# USBASP.net
KiCad netlist of a schematic drawn in EAGLE
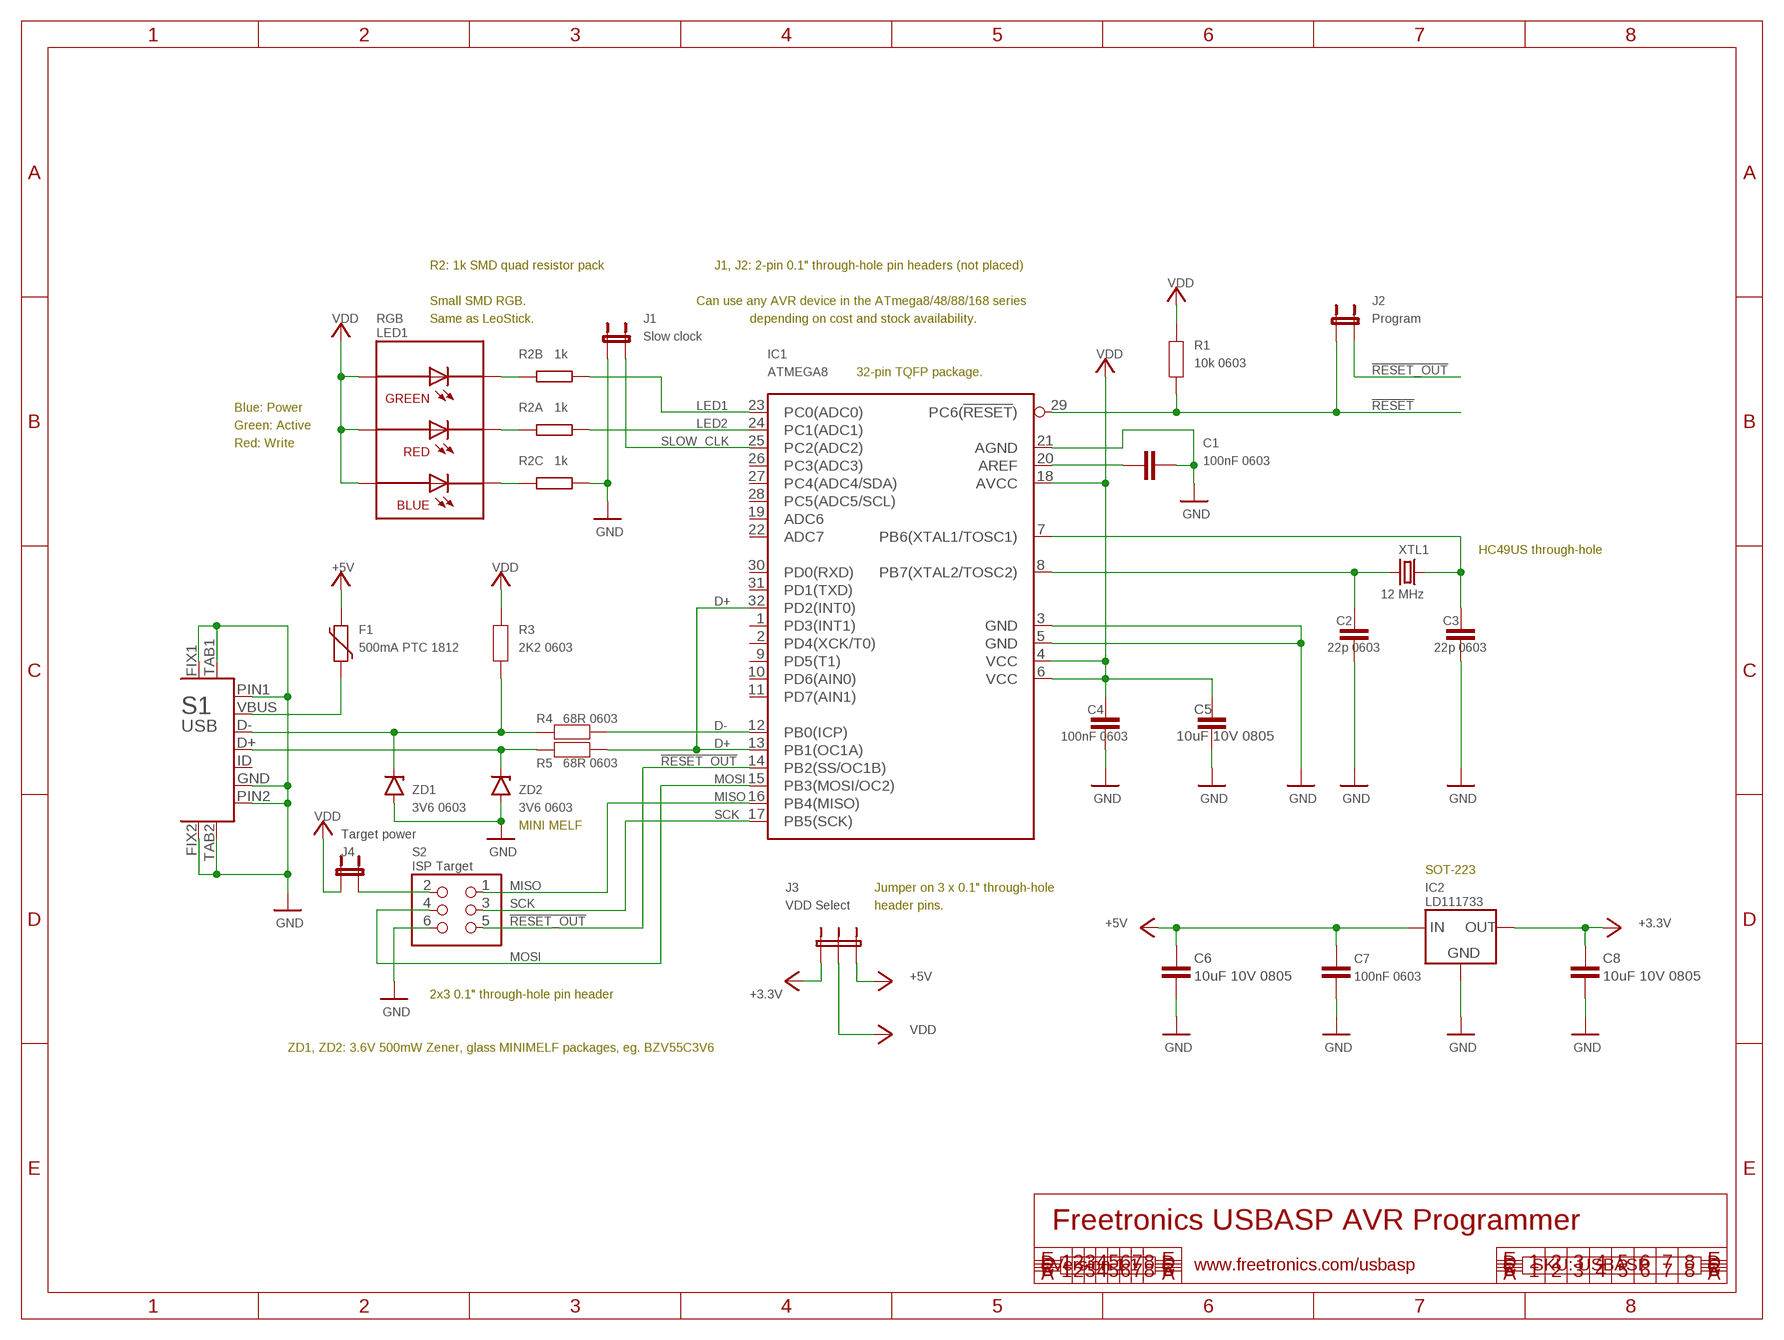
[diagram p0: schematic, sheet 1]

(export (version "E")
  (design (tool "Eeschema 10.0.6"))
  (components
    (comp (ref "C1")
      (value "100nF 0603")
      (footprint "eagle-import:0603")
      (libsource (lib "eagle-import") (part "CAP0603"))
    )
    (comp (ref "C2")
      (value "22p 0603")
      (footprint "eagle-import:0603")
      (libsource (lib "eagle-import") (part "CAP0603"))
    )
    (comp (ref "C3")
      (value "22p 0603")
      (footprint "eagle-import:0603")
      (libsource (lib "eagle-import") (part "CAP0603"))
    )
    (comp (ref "C4")
      (value "100nF 0603")
      (footprint "eagle-import:0603")
      (libsource (lib "eagle-import") (part "CAP0603"))
    )
    (comp (ref "C5")
      (value "10uF 10V 0805")
      (footprint "eagle-import:C0805")
      (libsource (lib "eagle-import") (part "C-EUC0805"))
    )
    (comp (ref "C6")
      (value "10uF 10V 0805")
      (footprint "eagle-import:C0805")
      (libsource (lib "eagle-import") (part "C-EUC0805"))
    )
    (comp (ref "C7")
      (value "100nF 0603")
      (footprint "eagle-import:0603")
      (libsource (lib "eagle-import") (part "CAP0603"))
    )
    (comp (ref "C8")
      (value "10uF 10V 0805")
      (footprint "eagle-import:C0805")
      (libsource (lib "eagle-import") (part "C-EUC0805"))
    )
    (comp (ref "F1")
      (value "500mA PTC 1812")
      (footprint "eagle-import:1812")
      (libsource (lib "eagle-import") (part "PTC"))
    )
    (comp (ref "IC1")
      (value "ATMEGA8")
      (footprint "eagle-import:TQFP32-08")
      (libsource (lib "eagle-import") (part "ATMEGA168"))
    )
    (comp (ref "IC2")
      (value "LD111733")
      (footprint "eagle-import:SOT-223")
      (libsource (lib "eagle-import") (part "LD1117-FIXED"))
    )
    (comp (ref "J1")
      (value "Slow clock")
      (footprint "eagle-import:HEADER_1X02")
      (libsource (lib "eagle-import") (part "JUMPER_PTH"))
    )
    (comp (ref "J2")
      (value "Program")
      (footprint "eagle-import:HEADER_1X02")
      (libsource (lib "eagle-import") (part "JUMPER_PTH"))
    )
    (comp (ref "J3")
      (value "VDD Select")
      (footprint "eagle-import:JUMPER_SPDT")
      (libsource (lib "eagle-import") (part "JUMPER_SPDT"))
    )
    (comp (ref "J4")
      (value "Target power")
      (footprint "eagle-import:HEADER_1X02")
      (libsource (lib "eagle-import") (part "JUMPER_PTH"))
    )
    (comp (ref "LED1")
      (value "RGB")
      (footprint "eagle-import:19-337")
      (libsource (lib "eagle-import") (part "RGBLEDSMT"))
    )
    (comp (ref "R1")
      (value "10k 0603")
      (footprint "eagle-import:0603")
      (libsource (lib "eagle-import") (part "RESISTOR0603"))
    )
    (comp (ref "R2")
      (value "1k")
      (footprint "eagle-import:CAY16")
      (libsource (lib "eagle-import") (part "CAY16"))
    )
    (comp (ref "R3")
      (value "2K2 0603")
      (footprint "eagle-import:0603")
      (libsource (lib "eagle-import") (part "RESISTOR0603"))
    )
    (comp (ref "R4")
      (value "68R 0603")
      (footprint "eagle-import:0603")
      (libsource (lib "eagle-import") (part "RESISTOR0603"))
    )
    (comp (ref "R5")
      (value "68R 0603")
      (footprint "eagle-import:0603")
      (libsource (lib "eagle-import") (part "RESISTOR0603"))
    )
    (comp (ref "S1")
      (value "USB")
      (footprint "eagle-import:USB-MICROB-MB05PMXX")
      (libsource (lib "eagle-import") (part "USB-6PSMT"))
    )
    (comp (ref "S2")
      (value "ISP Target")
      (footprint "eagle-import:HEADER_2X3")
      (libsource (lib "eagle-import") (part "HEADER_2X3"))
    )
    (comp (ref "XTL1")
      (value "12 MHz")
      (footprint "eagle-import:HC49US")
      (libsource (lib "eagle-import") (part "CRYSTALHC49US"))
    )
    (comp (ref "ZD1")
      (value "3V6 0603")
      (footprint "eagle-import:MINIMELF")
      (libsource (lib "eagle-import") (part "ZENERMINIMELF"))
    )
    (comp (ref "ZD2")
      (value "3V6 0603")
      (footprint "eagle-import:MINIMELF")
      (libsource (lib "eagle-import") (part "ZENERMINIMELF"))
    )
  )
  (nets
    (net (code "1") (name "+3.3V") (class "Default")
      (node (ref "C8") (pin "1") (pinfunction "1_1") (pintype "passive"))
      (node (ref "IC2") (pin "2") (pinfunction "OUT_2") (pintype "power_in"))
      (node (ref "IC2") (pin "4") (pinfunction "OUT_4") (pintype "power_in"))
      (node (ref "J3") (pin "1") (pinfunction "1_1") (pintype "passive"))
    )
    (net (code "2") (name "+5V") (class "Default")
      (node (ref "C6") (pin "1") (pinfunction "1_1") (pintype "passive"))
      (node (ref "C7") (pin "1") (pinfunction "1_1") (pintype "passive"))
      (node (ref "F1") (pin "2") (pinfunction "P$2_2") (pintype "bidirectional"))
      (node (ref "IC2") (pin "3") (pinfunction "IN_3") (pintype "input"))
      (node (ref "J3") (pin "3") (pinfunction "3_3") (pintype "passive"))
    )
    (net (code "3") (name "/D+") (class "Default")
      (node (ref "IC1") (pin "13") (pinfunction "PB1(OC1A)_13") (pintype "bidirectional"))
      (node (ref "IC1") (pin "32") (pinfunction "PD2(INT0)_32") (pintype "bidirectional"))
      (node (ref "R5") (pin "1") (pinfunction "1_1") (pintype "passive"))
    )
    (net (code "4") (name "/D-") (class "Default")
      (node (ref "IC1") (pin "12") (pinfunction "PB0(ICP)_12") (pintype "bidirectional"))
      (node (ref "R4") (pin "1") (pinfunction "1_1") (pintype "passive"))
    )
    (net (code "5") (name "/LED1") (class "Default")
      (node (ref "IC1") (pin "23") (pinfunction "PC0(ADC0)_23") (pintype "bidirectional"))
      (node (ref "R2") (pin "2") (pinfunction "1_2") (pintype "passive"))
    )
    (net (code "6") (name "/LED2") (class "Default")
      (node (ref "IC1") (pin "24") (pinfunction "PC1(ADC1)_24") (pintype "bidirectional"))
      (node (ref "R2") (pin "1") (pinfunction "1_1") (pintype "passive"))
    )
    (net (code "7") (name "/MISO") (class "Default")
      (node (ref "IC1") (pin "16") (pinfunction "PB4(MISO)_16") (pintype "bidirectional"))
      (node (ref "S2") (pin "1") (pinfunction "1_1") (pintype "passive"))
    )
    (net (code "8") (name "/MOSI") (class "Default")
      (node (ref "IC1") (pin "15") (pinfunction "PB3(MOSI/OC2)_15") (pintype "bidirectional"))
      (node (ref "S2") (pin "4") (pinfunction "4_4") (pintype "passive"))
    )
    (net (code "9") (name "/SCK") (class "Default")
      (node (ref "IC1") (pin "17") (pinfunction "PB5(SCK)_17") (pintype "bidirectional"))
      (node (ref "S2") (pin "3") (pinfunction "3_3") (pintype "passive"))
    )
    (net (code "10") (name "/SLOW_CLK") (class "Default")
      (node (ref "IC1") (pin "25") (pinfunction "PC2(ADC2)_25") (pintype "bidirectional"))
      (node (ref "J1") (pin "2") (pinfunction "2_2") (pintype "passive"))
    )
    (net (code "11") (name "/~{RESET_OUT}") (class "Default")
      (node (ref "IC1") (pin "14") (pinfunction "PB2(SS/OC1B)_14") (pintype "bidirectional"))
      (node (ref "J2") (pin "2") (pinfunction "2_2") (pintype "passive"))
      (node (ref "S2") (pin "5") (pinfunction "5_5") (pintype "passive"))
    )
    (net (code "12") (name "/~{RESET}") (class "Default")
      (node (ref "IC1") (pin "29") (pinfunction "PC6(~{RESET})_29") (pintype "bidirectional"))
      (node (ref "J2") (pin "1") (pinfunction "1_1") (pintype "passive"))
      (node (ref "R1") (pin "1") (pinfunction "1_1") (pintype "passive"))
    )
    (net (code "13") (name "GND") (class "Default")
      (node (ref "C1") (pin "2") (pinfunction "2_2") (pintype "passive"))
      (node (ref "C2") (pin "1") (pinfunction "1_1") (pintype "passive"))
      (node (ref "C3") (pin "1") (pinfunction "1_1") (pintype "passive"))
      (node (ref "C4") (pin "2") (pinfunction "2_2") (pintype "passive"))
      (node (ref "C5") (pin "2") (pinfunction "2_2") (pintype "passive"))
      (node (ref "C6") (pin "2") (pinfunction "2_2") (pintype "passive"))
      (node (ref "C7") (pin "2") (pinfunction "2_2") (pintype "passive"))
      (node (ref "C8") (pin "2") (pinfunction "2_2") (pintype "passive"))
      (node (ref "IC1") (pin "21") (pinfunction "AGND_21") (pintype "bidirectional"))
      (node (ref "IC1") (pin "3") (pinfunction "GND_3") (pintype "bidirectional"))
      (node (ref "IC1") (pin "5") (pinfunction "GND_5") (pintype "bidirectional"))
      (node (ref "IC2") (pin "1") (pinfunction "GND_1") (pintype "input"))
      (node (ref "J1") (pin "1") (pinfunction "1_1") (pintype "passive"))
      (node (ref "R2") (pin "3") (pinfunction "1_3") (pintype "passive"))
      (node (ref "S1") (pin "FIX1") (pinfunction "FIX1_FIX1") (pintype "bidirectional"))
      (node (ref "S1") (pin "FIX2") (pinfunction "FIX2_FIX2") (pintype "bidirectional"))
      (node (ref "S1") (pin "GND") (pinfunction "GND_GND") (pintype "bidirectional"))
      (node (ref "S1") (pin "PIN1") (pinfunction "PIN1_PIN1") (pintype "bidirectional"))
      (node (ref "S1") (pin "PIN2") (pinfunction "PIN2_PIN2") (pintype "bidirectional"))
      (node (ref "S1") (pin "TAB1") (pinfunction "TAB1_TAB1") (pintype "bidirectional"))
      (node (ref "S1") (pin "TAB2") (pinfunction "TAB2_TAB2") (pintype "bidirectional"))
      (node (ref "S2") (pin "6") (pinfunction "6_6") (pintype "passive"))
      (node (ref "ZD1") (pin "A") (pinfunction "A_A") (pintype "passive"))
      (node (ref "ZD2") (pin "A") (pinfunction "A_A") (pintype "passive"))
    )
    (net (code "14") (name "Net-(F1-P$1)") (class "Default")
      (node (ref "F1") (pin "1") (pinfunction "P$1_1") (pintype "bidirectional"))
      (node (ref "S1") (pin "VBUS") (pinfunction "VBUS_VBUS") (pintype "bidirectional"))
    )
    (net (code "15") (name "Net-(IC1-AREF)") (class "Default")
      (node (ref "C1") (pin "1") (pinfunction "1_1") (pintype "passive"))
      (node (ref "IC1") (pin "20") (pinfunction "AREF_20") (pintype "bidirectional"))
    )
    (net (code "16") (name "Net-(IC1-PB6(XTAL1{slash}TOSC1))") (class "Default")
      (node (ref "C3") (pin "2") (pinfunction "2_2") (pintype "passive"))
      (node (ref "IC1") (pin "7") (pinfunction "PB6(XTAL1/TOSC1)_7") (pintype "bidirectional"))
      (node (ref "XTL1") (pin "2") (pinfunction "2_2") (pintype "passive"))
    )
    (net (code "17") (name "Net-(IC1-PB7(XTAL2{slash}TOSC2))") (class "Default")
      (node (ref "C2") (pin "2") (pinfunction "2_2") (pintype "passive"))
      (node (ref "IC1") (pin "8") (pinfunction "PB7(XTAL2/TOSC2)_8") (pintype "bidirectional"))
      (node (ref "XTL1") (pin "1") (pinfunction "1_1") (pintype "passive"))
    )
    (net (code "18") (name "Net-(J4-Pad2)") (class "Default")
      (node (ref "J4") (pin "2") (pinfunction "2_2") (pintype "passive"))
      (node (ref "S2") (pin "2") (pinfunction "2_2") (pintype "passive"))
    )
    (net (code "19") (name "Net-(LED1-C-B)") (class "Default")
      (node (ref "LED1") (pin "1") (pinfunction "C-B_1") (pintype "passive"))
      (node (ref "R2") (pin "6") (pinfunction "2_6") (pintype "passive"))
    )
    (net (code "20") (name "Net-(LED1-C-G)") (class "Default")
      (node (ref "LED1") (pin "3") (pinfunction "C-G_3") (pintype "passive"))
      (node (ref "R2") (pin "7") (pinfunction "2_7") (pintype "passive"))
    )
    (net (code "21") (name "Net-(LED1-C-R)") (class "Default")
      (node (ref "LED1") (pin "2") (pinfunction "C-R_2") (pintype "passive"))
      (node (ref "R2") (pin "8") (pinfunction "2_8") (pintype "passive"))
    )
    (net (code "22") (name "Net-(R3-Pad1)") (class "Default")
      (node (ref "R3") (pin "1") (pinfunction "1_1") (pintype "passive"))
      (node (ref "R4") (pin "2") (pinfunction "2_2") (pintype "passive"))
      (node (ref "S1") (pin "D-") (pinfunction "D-_D-") (pintype "bidirectional"))
      (node (ref "ZD1") (pin "K") (pinfunction "K_K") (pintype "passive"))
    )
    (net (code "23") (name "Net-(R5-Pad2)") (class "Default")
      (node (ref "R5") (pin "2") (pinfunction "2_2") (pintype "passive"))
      (node (ref "S1") (pin "D+") (pinfunction "D+_D+") (pintype "bidirectional"))
      (node (ref "ZD2") (pin "K") (pinfunction "K_K") (pintype "passive"))
    )
    (net (code "24") (name "VDD") (class "Default")
      (node (ref "C4") (pin "1") (pinfunction "1_1") (pintype "passive"))
      (node (ref "C5") (pin "1") (pinfunction "1_1") (pintype "passive"))
      (node (ref "IC1") (pin "18") (pinfunction "AVCC_18") (pintype "bidirectional"))
      (node (ref "IC1") (pin "4") (pinfunction "VCC_4") (pintype "bidirectional"))
      (node (ref "IC1") (pin "6") (pinfunction "VCC_6") (pintype "bidirectional"))
      (node (ref "J3") (pin "2") (pinfunction "2_2") (pintype "passive"))
      (node (ref "J4") (pin "1") (pinfunction "1_1") (pintype "passive"))
      (node (ref "LED1") (pin "4") (pinfunction "A-B_4") (pintype "passive"))
      (node (ref "LED1") (pin "5") (pinfunction "A-R_5") (pintype "passive"))
      (node (ref "LED1") (pin "6") (pinfunction "A-G_6") (pintype "passive"))
      (node (ref "R1") (pin "2") (pinfunction "2_2") (pintype "passive"))
      (node (ref "R3") (pin "2") (pinfunction "2_2") (pintype "passive"))
    )
    (net (code "25") (name "unconnected-(IC1-ADC6-Pad19)") (class "Default")
      (node (ref "IC1") (pin "19") (pinfunction "ADC6_19") (pintype "bidirectional"))
    )
    (net (code "26") (name "unconnected-(IC1-ADC7-Pad22)") (class "Default")
      (node (ref "IC1") (pin "22") (pinfunction "ADC7_22") (pintype "bidirectional"))
    )
    (net (code "27") (name "unconnected-(IC1-PC3(ADC3)-Pad26)") (class "Default")
      (node (ref "IC1") (pin "26") (pinfunction "PC3(ADC3)_26") (pintype "bidirectional"))
    )
    (net (code "28") (name "unconnected-(IC1-PC4(ADC4{slash}SDA)-Pad27)") (class "Default")
      (node (ref "IC1") (pin "27") (pinfunction "PC4(ADC4/SDA)_27") (pintype "bidirectional"))
    )
    (net (code "29") (name "unconnected-(IC1-PC5(ADC5{slash}SCL)-Pad28)") (class "Default")
      (node (ref "IC1") (pin "28") (pinfunction "PC5(ADC5/SCL)_28") (pintype "bidirectional"))
    )
    (net (code "30") (name "unconnected-(IC1-PD0(RXD)-Pad30)") (class "Default")
      (node (ref "IC1") (pin "30") (pinfunction "PD0(RXD)_30") (pintype "bidirectional"))
    )
    (net (code "31") (name "unconnected-(IC1-PD1(TXD)-Pad31)") (class "Default")
      (node (ref "IC1") (pin "31") (pinfunction "PD1(TXD)_31") (pintype "bidirectional"))
    )
    (net (code "32") (name "unconnected-(IC1-PD3(INT1)-Pad1)") (class "Default")
      (node (ref "IC1") (pin "1") (pinfunction "PD3(INT1)_1") (pintype "bidirectional"))
    )
    (net (code "33") (name "unconnected-(IC1-PD4(XCK{slash}T0)-Pad2)") (class "Default")
      (node (ref "IC1") (pin "2") (pinfunction "PD4(XCK/T0)_2") (pintype "bidirectional"))
    )
    (net (code "34") (name "unconnected-(IC1-PD5(T1)-Pad9)") (class "Default")
      (node (ref "IC1") (pin "9") (pinfunction "PD5(T1)_9") (pintype "bidirectional"))
    )
    (net (code "35") (name "unconnected-(IC1-PD6(AIN0)-Pad10)") (class "Default")
      (node (ref "IC1") (pin "10") (pinfunction "PD6(AIN0)_10") (pintype "bidirectional"))
    )
    (net (code "36") (name "unconnected-(IC1-PD7(AIN1)-Pad11)") (class "Default")
      (node (ref "IC1") (pin "11") (pinfunction "PD7(AIN1)_11") (pintype "bidirectional"))
    )
    (net (code "37") (name "unconnected-(S1-PadID)") (class "Default")
      (node (ref "S1") (pin "ID") (pinfunction "ID_ID") (pintype "bidirectional"))
    )
  )
)
